# STC12_CH340E.net
KiCad netlist of a schematic drawn in Altium Designer
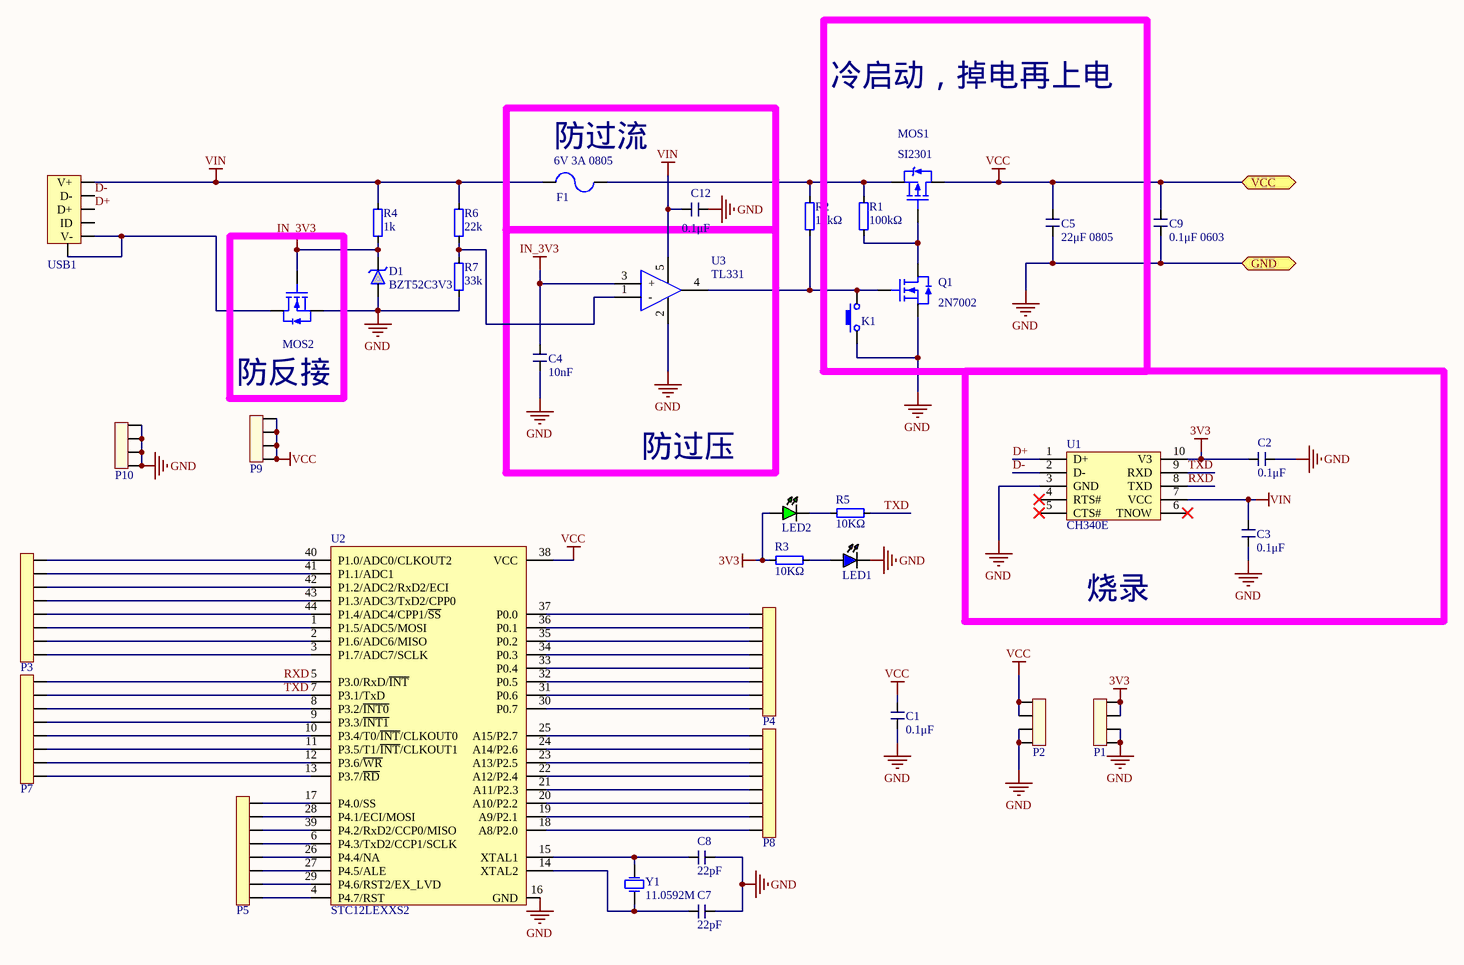
[diagram p0: STC12+CH340E.SchDoc]

(export (version "E")
  (design (tool "Eeschema 10.0.6"))
  (components
    (comp (ref "C1") (value "0.1μF") (footprint "C_0603") (libsource (lib "节能库") (part "C_0603")))
    (comp (ref "C2") (value "0.1μF") (footprint "C_0603") (libsource (lib "节能库") (part "C_0603")))
    (comp (ref "C3") (value "0.1μF") (footprint "C_0603") (libsource (lib "节能库") (part "C_0603")))
    (comp (ref "C4") (value "10nF") (footprint "C_0603") (libsource (lib "节能库") (part "C_0603")))
    (comp (ref "C5") (value "22μF 0805") (footprint "C_0805") (libsource (lib "节能库") (part "C_0805")))
    (comp (ref "C7") (value "22pF") (footprint "C_0603") (libsource (lib "节能库") (part "C_0603")))
    (comp (ref "C8") (value "22pF") (footprint "C_0603") (libsource (lib "节能库") (part "C_0603")))
    (comp (ref "C9") (value "0.1μF 0603") (footprint "C_0603") (libsource (lib "节能库") (part "C_0603")))
    (comp (ref "C12") (value "0.1μF") (footprint "C_0603") (libsource (lib "节能库") (part "C_0603")))
    (comp (ref "D1") (value "BZT52C3V3") (footprint "SOD_123") (libsource (lib "节能库") (part "BZT52CxVx")))
    (comp (ref "F1") (value "6V 3A 0805") (footprint "FB_0805") (libsource (lib "节能库") (part "FUSE_0805")))
    (comp (ref "K1")
      (value "TACT SWITCH_2_SMD")
      (footprint "TACT SWITCH_2_SMD")
      (libsource (lib "节能库") (part "TACT SWITCH_2_SMD"))
    )
    (comp (ref "LED1")
      (value "LED_0603-B")
      (footprint "LED_0603-B")
      (libsource (lib "节能库") (part "LED_0603-B"))
    )
    (comp (ref "LED2")
      (value "LED_0603-G")
      (footprint "LED_0603-G")
      (libsource (lib "节能库") (part "LED_0603-G"))
    )
    (comp (ref "MOS1") (value "SI2301") (footprint "SOT_23_3") (libsource (lib "节能库") (part "SI2301")))
    (comp (ref "MOS2") (value "AO3400A") (footprint "SOT_23_3") (libsource (lib "节能库") (part "AO3400A")))
    (comp (ref "P1") (value "PIN4") (footprint "PIN_4") (libsource (lib "") (part "PIN4_2")))
    (comp (ref "P2") (value "PIN4") (footprint "PIN_4") (libsource (lib "节能库") (part "PIN4")))
    (comp (ref "P3") (value "PIN8") (footprint "PIN_8") (libsource (lib "节能库") (part "PIN8")))
    (comp (ref "P4") (value "PIN8") (footprint "PIN_8") (libsource (lib "") (part "PIN8_1")))
    (comp (ref "P5") (value "PIN8") (footprint "PIN_8") (libsource (lib "节能库") (part "PIN8")))
    (comp (ref "P7") (value "PIN8") (footprint "PIN_8") (libsource (lib "节能库") (part "PIN8")))
    (comp (ref "P8") (value "PIN8") (footprint "PIN_8") (libsource (lib "") (part "PIN8_1")))
    (comp (ref "P9") (value "PIN4") (footprint "PIN_4") (libsource (lib "") (part "PIN4_1")))
    (comp (ref "P10") (value "PIN4") (footprint "PIN_4") (libsource (lib "") (part "PIN4_1")))
    (comp (ref "Q1") (value "2N7002") (footprint "SOT_23_3") (libsource (lib "节能库") (part "2N7002")))
    (comp (ref "R1") (value "100kΩ") (footprint "R_0603") (libsource (lib "节能库") (part "R_0603")))
    (comp (ref "R2") (value "10kΩ") (footprint "R_0603") (libsource (lib "节能库") (part "R_0603")))
    (comp (ref "R3") (value "10KΩ") (footprint "R_0603") (libsource (lib "节能库") (part "R_0603")))
    (comp (ref "R4") (value "1k") (footprint "R_0603") (libsource (lib "节能库") (part "R_0603")))
    (comp (ref "R5") (value "10KΩ") (footprint "R_0603") (libsource (lib "节能库") (part "R_0603")))
    (comp (ref "R6") (value "22k") (footprint "R_0603") (libsource (lib "节能库") (part "R_0603")))
    (comp (ref "R7") (value "33k") (footprint "R_0603") (libsource (lib "节能库") (part "R_0603")))
    (comp (ref "U1") (value "CH340E") (footprint "MSOP_10") (libsource (lib "节能库") (part "CH340E")))
    (comp (ref "U2")
      (value "STC12LEXXS2")
      (footprint "LQFP_44")
      (libsource (lib "节能库") (part "STC12LE5AXXS2 - LQPF44"))
    )
    (comp (ref "U3") (value "TL331") (footprint "SOT_23_5") (libsource (lib "节能库") (part "TL331")))
    (comp (ref "USB1")
      (value "MICRO USB B")
      (footprint "MICRO USB B")
      (libsource (lib "节能库") (part "MICRO USB B"))
    )
    (comp (ref "Y1")
      (value "11.0592M")
      (footprint "Crystal_HC_49US")
      (libsource (lib "节能库") (part "Crystal_HC_49US"))
    )
  )
  (nets
    (net (code "1") (name "/D+") (class "Default")
      (node (ref "U1") (pin "1") (pinfunction "D+_1") (pintype "passive"))
      (node (ref "USB1") (pin "3") (pinfunction "D+_3") (pintype "passive"))
    )
    (net (code "2") (name "/D-") (class "Default")
      (node (ref "U1") (pin "2") (pinfunction "D-_2") (pintype "passive"))
      (node (ref "USB1") (pin "2") (pinfunction "D-_2") (pintype "passive"))
    )
    (net (code "3") (name "/RXD") (class "Default")
      (node (ref "P7") (pin "1") (pinfunction "1_1") (pintype "passive"))
      (node (ref "U1") (pin "8") (pinfunction "TXD_8") (pintype "passive"))
      (node (ref "U2") (pin "5") (pinfunction "P3.0/RxD/~{INT}_5") (pintype "passive"))
    )
    (net (code "4") (name "/TXD") (class "Default")
      (node (ref "P7") (pin "2") (pinfunction "2_2") (pintype "passive"))
      (node (ref "R5") (pin "2") (pintype "passive"))
      (node (ref "U1") (pin "9") (pinfunction "RXD_9") (pintype "passive"))
      (node (ref "U2") (pin "7") (pinfunction "P3.1/TxD_7") (pintype "passive"))
    )
    (net (code "5") (name "3V3") (class "Default")
      (node (ref "C2") (pin "2") (pinfunction "2_2") (pintype "passive"))
      (node (ref "LED2") (pin "1") (pinfunction "1_1") (pintype "passive"))
      (node (ref "P1") (pin "3") (pinfunction "3_3") (pintype "passive"))
      (node (ref "P1") (pin "4") (pinfunction "4_4") (pintype "passive"))
      (node (ref "R3") (pin "1") (pintype "passive"))
      (node (ref "U1") (pin "10") (pinfunction "V3_10") (pintype "passive"))
    )
    (net (code "6") (name "GND") (class "Default")
      (node (ref "C1") (pin "2") (pinfunction "2_2") (pintype "passive"))
      (node (ref "C12") (pin "2") (pinfunction "2_2") (pintype "passive"))
      (node (ref "C2") (pin "1") (pinfunction "1_1") (pintype "passive"))
      (node (ref "C3") (pin "1") (pinfunction "1_1") (pintype "passive"))
      (node (ref "C4") (pin "2") (pinfunction "2_2") (pintype "passive"))
      (node (ref "C5") (pin "2") (pinfunction "2_2") (pintype "passive"))
      (node (ref "C7") (pin "2") (pinfunction "2_2") (pintype "passive"))
      (node (ref "C8") (pin "2") (pinfunction "2_2") (pintype "passive"))
      (node (ref "C9") (pin "2") (pinfunction "2_2") (pintype "passive"))
      (node (ref "D1") (pin "1") (pinfunction "A_1") (pintype "passive"))
      (node (ref "K1") (pin "1") (pinfunction "1_1") (pintype "passive"))
      (node (ref "LED1") (pin "2") (pinfunction "2_2") (pintype "passive"))
      (node (ref "MOS2") (pin "2") (pinfunction "S_2") (pintype "passive"))
      (node (ref "P1") (pin "1") (pinfunction "1_1") (pintype "passive"))
      (node (ref "P1") (pin "2") (pinfunction "2_2") (pintype "passive"))
      (node (ref "P10") (pin "1") (pinfunction "1_1") (pintype "passive"))
      (node (ref "P10") (pin "2") (pinfunction "2_2") (pintype "passive"))
      (node (ref "P10") (pin "3") (pinfunction "3_3") (pintype "passive"))
      (node (ref "P10") (pin "4") (pinfunction "4_4") (pintype "passive"))
      (node (ref "P2") (pin "1") (pinfunction "1_1") (pintype "passive"))
      (node (ref "P2") (pin "2") (pinfunction "2_2") (pintype "passive"))
      (node (ref "Q1") (pin "2") (pinfunction "S_2") (pintype "passive"))
      (node (ref "R7") (pin "1") (pintype "passive"))
      (node (ref "U1") (pin "3") (pinfunction "GND_3") (pintype "passive"))
      (node (ref "U2") (pin "16") (pinfunction "GND_16") (pintype "passive"))
      (node (ref "U3") (pin "2") (pinfunction "GND_2") (pintype "passive"))
    )
    (net (code "7") (name "IN_3V3") (class "Default")
      (node (ref "C4") (pin "1") (pinfunction "1_1") (pintype "passive"))
      (node (ref "D1") (pin "2") (pinfunction "K_2") (pintype "passive"))
      (node (ref "MOS2") (pin "1") (pinfunction "G_1") (pintype "passive"))
      (node (ref "R4") (pin "1") (pintype "passive"))
      (node (ref "U3") (pin "3") (pinfunction "+_3") (pintype "passive"))
    )
    (net (code "8") (name "Net-(LED1-Pad1)") (class "Default")
      (node (ref "LED1") (pin "1") (pinfunction "1_1") (pintype "passive"))
      (node (ref "R3") (pin "2") (pintype "passive"))
    )
    (net (code "9") (name "Net-(LED2-Pad2)") (class "Default")
      (node (ref "LED2") (pin "2") (pinfunction "2_2") (pintype "passive"))
      (node (ref "R5") (pin "1") (pintype "passive"))
    )
    (net (code "10") (name "Net-(MOS1-G)") (class "Default")
      (node (ref "MOS1") (pin "1") (pinfunction "G_1") (pintype "passive"))
      (node (ref "Q1") (pin "3") (pinfunction "D_3") (pintype "passive"))
      (node (ref "R1") (pin "1") (pintype "passive"))
    )
    (net (code "11") (name "Net-(MOS1-S)") (class "Default")
      (node (ref "F1") (pin "2") (pinfunction "2_2") (pintype "passive"))
      (node (ref "MOS1") (pin "2") (pinfunction "S_2") (pintype "passive"))
      (node (ref "R1") (pin "2") (pintype "passive"))
      (node (ref "R2") (pin "2") (pintype "passive"))
    )
    (net (code "12") (name "Net-(MOS2-D)") (class "Default")
      (node (ref "MOS2") (pin "3") (pinfunction "D_3") (pintype "passive"))
      (node (ref "USB1") (pin "0") (pinfunction "GND_0") (pintype "passive"))
      (node (ref "USB1") (pin "5") (pinfunction "V-_5") (pintype "passive"))
    )
    (net (code "13") (name "Net-(Q1-G)") (class "Default")
      (node (ref "K1") (pin "2") (pinfunction "2_2") (pintype "passive"))
      (node (ref "Q1") (pin "1") (pinfunction "G_1") (pintype "passive"))
      (node (ref "R2") (pin "1") (pintype "passive"))
      (node (ref "U3") (pin "4") (pinfunction "OUT_4") (pintype "passive"))
    )
    (net (code "14") (name "Net-(U2-A8{slash}P2.0)") (class "Default")
      (node (ref "P8") (pin "1") (pinfunction "1_1") (pintype "passive"))
      (node (ref "U2") (pin "18") (pinfunction "A8/P2.0_18") (pintype "passive"))
    )
    (net (code "15") (name "Net-(U2-A9{slash}P2.1)") (class "Default")
      (node (ref "P8") (pin "2") (pinfunction "2_2") (pintype "passive"))
      (node (ref "U2") (pin "19") (pinfunction "A9/P2.1_19") (pintype "passive"))
    )
    (net (code "16") (name "Net-(U2-A10{slash}P2.2)") (class "Default")
      (node (ref "P8") (pin "3") (pinfunction "3_3") (pintype "passive"))
      (node (ref "U2") (pin "20") (pinfunction "A10/P2.2_20") (pintype "passive"))
    )
    (net (code "17") (name "Net-(U2-A11{slash}P2.3)") (class "Default")
      (node (ref "P8") (pin "4") (pinfunction "4_4") (pintype "passive"))
      (node (ref "U2") (pin "21") (pinfunction "A11/P2.3_21") (pintype "passive"))
    )
    (net (code "18") (name "Net-(U2-A12{slash}P2.4)") (class "Default")
      (node (ref "P8") (pin "5") (pinfunction "5_5") (pintype "passive"))
      (node (ref "U2") (pin "22") (pinfunction "A12/P2.4_22") (pintype "passive"))
    )
    (net (code "19") (name "Net-(U2-A13{slash}P2.5)") (class "Default")
      (node (ref "P8") (pin "6") (pinfunction "6_6") (pintype "passive"))
      (node (ref "U2") (pin "23") (pinfunction "A13/P2.5_23") (pintype "passive"))
    )
    (net (code "20") (name "Net-(U2-A14{slash}P2.6)") (class "Default")
      (node (ref "P8") (pin "7") (pinfunction "7_7") (pintype "passive"))
      (node (ref "U2") (pin "24") (pinfunction "A14/P2.6_24") (pintype "passive"))
    )
    (net (code "21") (name "Net-(U2-A15{slash}P2.7)") (class "Default")
      (node (ref "P8") (pin "8") (pinfunction "8_8") (pintype "passive"))
      (node (ref "U2") (pin "25") (pinfunction "A15/P2.7_25") (pintype "passive"))
    )
    (net (code "22") (name "Net-(U2-P0.0)") (class "Default")
      (node (ref "P4") (pin "8") (pinfunction "8_8") (pintype "passive"))
      (node (ref "U2") (pin "37") (pinfunction "P0.0_37") (pintype "passive"))
    )
    (net (code "23") (name "Net-(U2-P0.1)") (class "Default")
      (node (ref "P4") (pin "7") (pinfunction "7_7") (pintype "passive"))
      (node (ref "U2") (pin "36") (pinfunction "P0.1_36") (pintype "passive"))
    )
    (net (code "24") (name "Net-(U2-P0.2)") (class "Default")
      (node (ref "P4") (pin "6") (pinfunction "6_6") (pintype "passive"))
      (node (ref "U2") (pin "35") (pinfunction "P0.2_35") (pintype "passive"))
    )
    (net (code "25") (name "Net-(U2-P0.3)") (class "Default")
      (node (ref "P4") (pin "5") (pinfunction "5_5") (pintype "passive"))
      (node (ref "U2") (pin "34") (pinfunction "P0.3_34") (pintype "passive"))
    )
    (net (code "26") (name "Net-(U2-P0.4)") (class "Default")
      (node (ref "P4") (pin "4") (pinfunction "4_4") (pintype "passive"))
      (node (ref "U2") (pin "33") (pinfunction "P0.4_33") (pintype "passive"))
    )
    (net (code "27") (name "Net-(U2-P0.5)") (class "Default")
      (node (ref "P4") (pin "3") (pinfunction "3_3") (pintype "passive"))
      (node (ref "U2") (pin "32") (pinfunction "P0.5_32") (pintype "passive"))
    )
    (net (code "28") (name "Net-(U2-P0.6)") (class "Default")
      (node (ref "P4") (pin "2") (pinfunction "2_2") (pintype "passive"))
      (node (ref "U2") (pin "31") (pinfunction "P0.6_31") (pintype "passive"))
    )
    (net (code "29") (name "Net-(U2-P0.7)") (class "Default")
      (node (ref "P4") (pin "1") (pinfunction "1_1") (pintype "passive"))
      (node (ref "U2") (pin "30") (pinfunction "P0.7_30") (pintype "passive"))
    )
    (net (code "30") (name "Net-(U2-P1.0{slash}ADC0{slash}CLKOUT2)") (class "Default")
      (node (ref "P3") (pin "1") (pinfunction "1_1") (pintype "passive"))
      (node (ref "U2") (pin "40") (pinfunction "P1.0/ADC0/CLKOUT2_40") (pintype "passive"))
    )
    (net (code "31") (name "Net-(U2-P1.1{slash}ADC1)") (class "Default")
      (node (ref "P3") (pin "2") (pinfunction "2_2") (pintype "passive"))
      (node (ref "U2") (pin "41") (pinfunction "P1.1/ADC1_41") (pintype "passive"))
    )
    (net (code "32") (name "Net-(U2-P1.2{slash}ADC2{slash}RxD2{slash}ECI)") (class "Default")
      (node (ref "P3") (pin "3") (pinfunction "3_3") (pintype "passive"))
      (node (ref "U2") (pin "42") (pinfunction "P1.2/ADC2/RxD2/ECI_42") (pintype "passive"))
    )
    (net (code "33") (name "Net-(U2-P1.3{slash}ADC3{slash}TxD2{slash}CPP0)") (class "Default")
      (node (ref "P3") (pin "4") (pinfunction "4_4") (pintype "passive"))
      (node (ref "U2") (pin "43") (pinfunction "P1.3/ADC3/TxD2/CPP0_43") (pintype "passive"))
    )
    (net (code "34") (name "Net-(U2-P1.4{slash}ADC4{slash}CPP1{slash}~{SS})") (class "Default")
      (node (ref "P3") (pin "5") (pinfunction "5_5") (pintype "passive"))
      (node (ref "U2") (pin "44") (pinfunction "P1.4/ADC4/CPP1/~{SS}_44") (pintype "passive"))
    )
    (net (code "35") (name "Net-(U2-P1.5{slash}ADC5{slash}MOSI)") (class "Default")
      (node (ref "P3") (pin "6") (pinfunction "6_6") (pintype "passive"))
      (node (ref "U2") (pin "1") (pinfunction "P1.5/ADC5/MOSI_1") (pintype "passive"))
    )
    (net (code "36") (name "Net-(U2-P1.6{slash}ADC6{slash}MISO)") (class "Default")
      (node (ref "P3") (pin "7") (pinfunction "7_7") (pintype "passive"))
      (node (ref "U2") (pin "2") (pinfunction "P1.6/ADC6/MISO_2") (pintype "passive"))
    )
    (net (code "37") (name "Net-(U2-P1.7{slash}ADC7{slash}SCLK)") (class "Default")
      (node (ref "P3") (pin "8") (pinfunction "8_8") (pintype "passive"))
      (node (ref "U2") (pin "3") (pinfunction "P1.7/ADC7/SCLK_3") (pintype "passive"))
    )
    (net (code "38") (name "Net-(U2-P3.2{slash}~{INT0})") (class "Default")
      (node (ref "P7") (pin "3") (pinfunction "3_3") (pintype "passive"))
      (node (ref "U2") (pin "8") (pinfunction "P3.2/~{INT0}_8") (pintype "passive"))
    )
    (net (code "39") (name "Net-(U2-P3.3{slash}~{INT1})") (class "Default")
      (node (ref "P7") (pin "4") (pinfunction "4_4") (pintype "passive"))
      (node (ref "U2") (pin "9") (pinfunction "P3.3/~{INT1}_9") (pintype "passive"))
    )
    (net (code "40") (name "Net-(U2-P3.4{slash}T0{slash}~{INT}{slash}CLKOUT0)") (class "Default")
      (node (ref "P7") (pin "5") (pinfunction "5_5") (pintype "passive"))
      (node (ref "U2") (pin "10") (pinfunction "P3.4/T0/~{INT}/CLKOUT0_10") (pintype "passive"))
    )
    (net (code "41") (name "Net-(U2-P3.5{slash}T1{slash}~{INT}{slash}CLKOUT1)") (class "Default")
      (node (ref "P7") (pin "6") (pinfunction "6_6") (pintype "passive"))
      (node (ref "U2") (pin "11") (pinfunction "P3.5/T1/~{INT}/CLKOUT1_11") (pintype "passive"))
    )
    (net (code "42") (name "Net-(U2-P3.6{slash}~{WR})") (class "Default")
      (node (ref "P7") (pin "7") (pinfunction "7_7") (pintype "passive"))
      (node (ref "U2") (pin "12") (pinfunction "P3.6/~{WR}_12") (pintype "passive"))
    )
    (net (code "43") (name "Net-(U2-P3.7{slash}~{RD})") (class "Default")
      (node (ref "P7") (pin "8") (pinfunction "8_8") (pintype "passive"))
      (node (ref "U2") (pin "13") (pinfunction "P3.7/~{RD}_13") (pintype "passive"))
    )
    (net (code "44") (name "Net-(U2-P4.0{slash}SS)") (class "Default")
      (node (ref "P5") (pin "1") (pinfunction "1_1") (pintype "passive"))
      (node (ref "U2") (pin "17") (pinfunction "P4.0/SS_17") (pintype "passive"))
    )
    (net (code "45") (name "Net-(U2-P4.1{slash}ECI{slash}MOSI)") (class "Default")
      (node (ref "P5") (pin "2") (pinfunction "2_2") (pintype "passive"))
      (node (ref "U2") (pin "28") (pinfunction "P4.1/ECI/MOSI_28") (pintype "passive"))
    )
    (net (code "46") (name "Net-(U2-P4.2{slash}RxD2{slash}CCP0{slash}MISO)") (class "Default")
      (node (ref "P5") (pin "3") (pinfunction "3_3") (pintype "passive"))
      (node (ref "U2") (pin "39") (pinfunction "P4.2/RxD2/CCP0/MISO_39") (pintype "passive"))
    )
    (net (code "47") (name "Net-(U2-P4.3{slash}TxD2{slash}CCP1{slash}SCLK)") (class "Default")
      (node (ref "P5") (pin "4") (pinfunction "4_4") (pintype "passive"))
      (node (ref "U2") (pin "6") (pinfunction "P4.3/TxD2/CCP1/SCLK_6") (pintype "passive"))
    )
    (net (code "48") (name "Net-(U2-P4.4{slash}NA)") (class "Default")
      (node (ref "P5") (pin "5") (pinfunction "5_5") (pintype "passive"))
      (node (ref "U2") (pin "26") (pinfunction "P4.4/NA_26") (pintype "passive"))
    )
    (net (code "49") (name "Net-(U2-P4.5{slash}ALE)") (class "Default")
      (node (ref "P5") (pin "6") (pinfunction "6_6") (pintype "passive"))
      (node (ref "U2") (pin "27") (pinfunction "P4.5/ALE_27") (pintype "passive"))
    )
    (net (code "50") (name "Net-(U2-P4.6{slash}RST2{slash}EX_LVD)") (class "Default")
      (node (ref "P5") (pin "7") (pinfunction "7_7") (pintype "passive"))
      (node (ref "U2") (pin "29") (pinfunction "P4.6/RST2/EX_LVD_29") (pintype "passive"))
    )
    (net (code "51") (name "Net-(U2-P4.7{slash}RST)") (class "Default")
      (node (ref "P5") (pin "8") (pinfunction "8_8") (pintype "passive"))
      (node (ref "U2") (pin "4") (pinfunction "P4.7/RST_4") (pintype "passive"))
    )
    (net (code "52") (name "Net-(U2-XTAL1)") (class "Default")
      (node (ref "C8") (pin "1") (pinfunction "1_1") (pintype "passive"))
      (node (ref "U2") (pin "15") (pinfunction "XTAL1_15") (pintype "passive"))
      (node (ref "Y1") (pin "2") (pinfunction "OSC2_2") (pintype "passive"))
    )
    (net (code "53") (name "Net-(U2-XTAL2)") (class "Default")
      (node (ref "C7") (pin "1") (pinfunction "1_1") (pintype "passive"))
      (node (ref "U2") (pin "14") (pinfunction "XTAL2_14") (pintype "passive"))
      (node (ref "Y1") (pin "1") (pinfunction "OSC1_1") (pintype "passive"))
    )
    (net (code "54") (name "Net-(U3--)") (class "Default")
      (node (ref "R6") (pin "1") (pintype "passive"))
      (node (ref "R7") (pin "2") (pintype "passive"))
      (node (ref "U3") (pin "1") (pinfunction "-_1") (pintype "passive"))
    )
    (net (code "55") (name "VCC") (class "Default")
      (node (ref "C1") (pin "1") (pinfunction "1_1") (pintype "passive"))
      (node (ref "C5") (pin "1") (pinfunction "1_1") (pintype "passive"))
      (node (ref "C9") (pin "1") (pinfunction "1_1") (pintype "passive"))
      (node (ref "MOS1") (pin "3") (pinfunction "D_3") (pintype "passive"))
      (node (ref "P2") (pin "3") (pinfunction "3_3") (pintype "passive"))
      (node (ref "P2") (pin "4") (pinfunction "4_4") (pintype "passive"))
      (node (ref "P9") (pin "1") (pinfunction "1_1") (pintype "passive"))
      (node (ref "P9") (pin "2") (pinfunction "2_2") (pintype "passive"))
      (node (ref "P9") (pin "3") (pinfunction "3_3") (pintype "passive"))
      (node (ref "P9") (pin "4") (pinfunction "4_4") (pintype "passive"))
      (node (ref "U2") (pin "38") (pinfunction "VCC_38") (pintype "passive"))
    )
    (net (code "56") (name "VIN") (class "Default")
      (node (ref "C12") (pin "1") (pinfunction "1_1") (pintype "passive"))
      (node (ref "C3") (pin "2") (pinfunction "2_2") (pintype "passive"))
      (node (ref "F1") (pin "1") (pinfunction "1_1") (pintype "passive"))
      (node (ref "R4") (pin "2") (pintype "passive"))
      (node (ref "R6") (pin "2") (pintype "passive"))
      (node (ref "U1") (pin "7") (pinfunction "VCC_7") (pintype "passive"))
      (node (ref "U3") (pin "5") (pinfunction "VCC_5") (pintype "passive"))
      (node (ref "USB1") (pin "1") (pinfunction "V+_1") (pintype "passive"))
    )
    (net (code "57") (name "unconnected-(U1-CTS#-Pad5)") (class "Default")
      (node (ref "U1") (pin "5") (pinfunction "CTS#_5") (pintype "passive+no_connect"))
    )
    (net (code "58") (name "unconnected-(U1-RTS#-Pad4)") (class "Default")
      (node (ref "U1") (pin "4") (pinfunction "RTS#_4") (pintype "passive+no_connect"))
    )
    (net (code "59") (name "unconnected-(U1-TNOW-Pad6)") (class "Default")
      (node (ref "U1") (pin "6") (pinfunction "TNOW_6") (pintype "passive+no_connect"))
    )
    (net (code "60") (name "unconnected-(USB1-ID-Pad4)") (class "Default")
      (node (ref "USB1") (pin "4") (pinfunction "ID_4") (pintype "passive"))
    )
  )
)
